# WS2812_MATRIX_6.net
KiCad netlist of a schematic drawn in Altium Designer
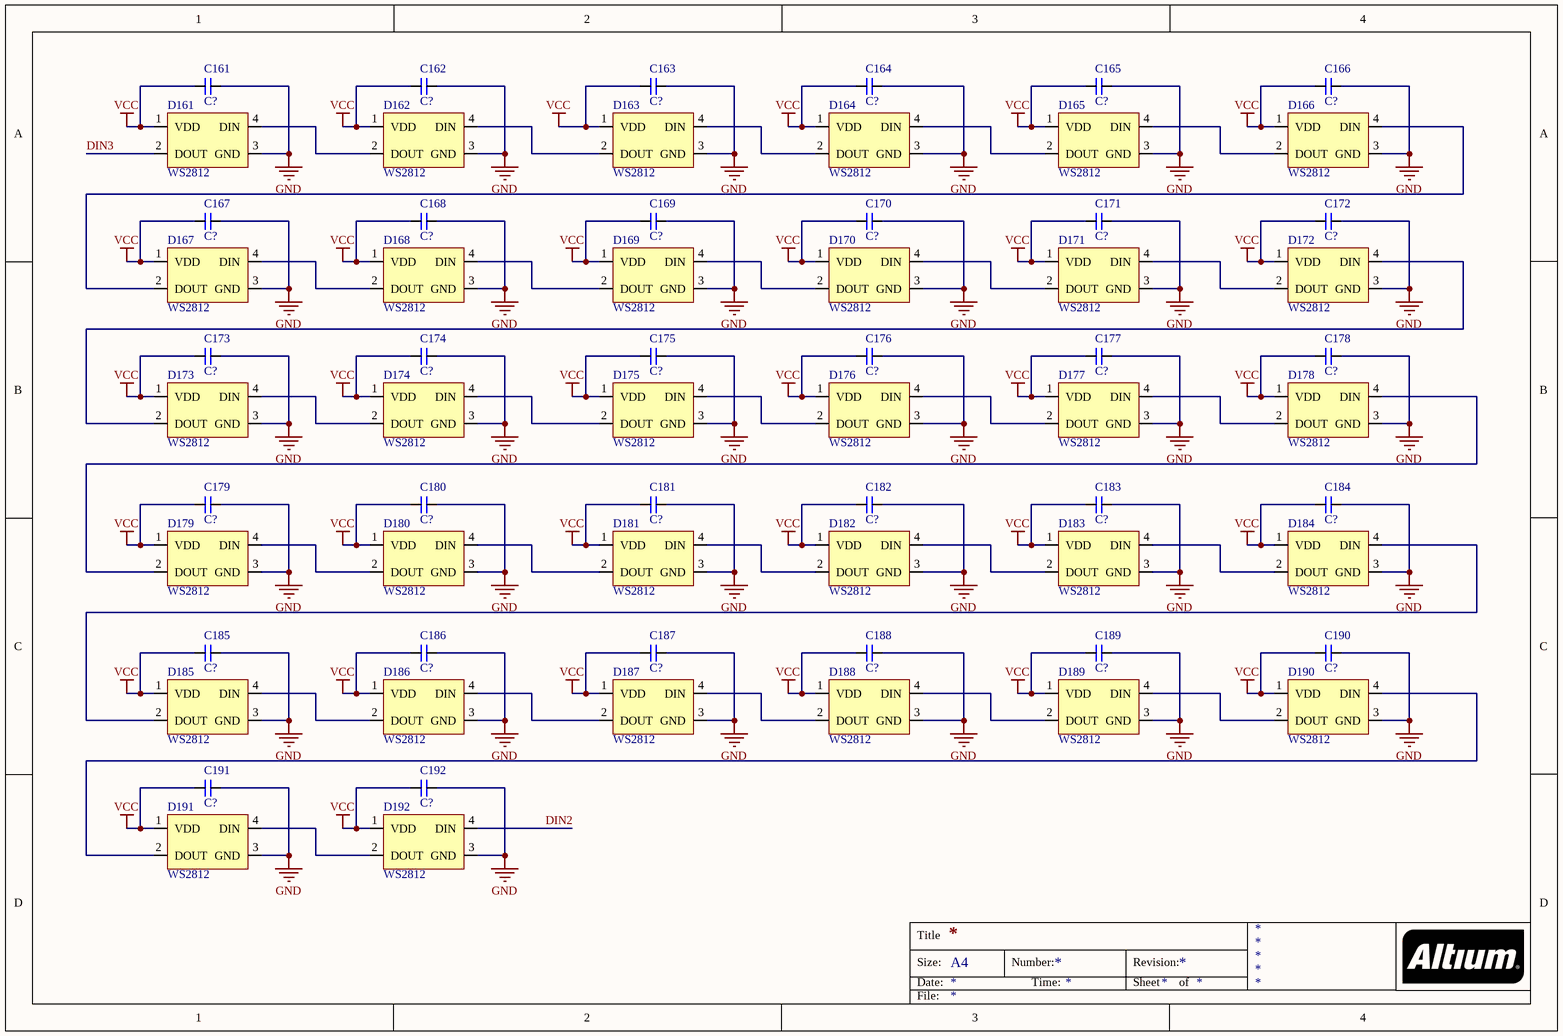
[diagram p0: WS2812_MATRIX_6.SchDoc]

(export (version "E")
  (design (tool "Eeschema 10.0.6"))
  (components
    (comp (ref "C161")
      (value "C?")
      (footprint "C0603")
      (description "Cap")
      (libsource (lib "SCH_Bacsic") (part "CAP"))
    )
    (comp (ref "C162")
      (value "C?")
      (footprint "C0603")
      (description "Cap")
      (libsource (lib "SCH_Bacsic") (part "CAP"))
    )
    (comp (ref "C163")
      (value "C?")
      (footprint "C0603")
      (description "Cap")
      (libsource (lib "SCH_Bacsic") (part "CAP"))
    )
    (comp (ref "C164")
      (value "C?")
      (footprint "C0603")
      (description "Cap")
      (libsource (lib "SCH_Bacsic") (part "CAP"))
    )
    (comp (ref "C165")
      (value "C?")
      (footprint "C0603")
      (description "Cap")
      (libsource (lib "SCH_Bacsic") (part "CAP"))
    )
    (comp (ref "C166")
      (value "C?")
      (footprint "C0603")
      (description "Cap")
      (libsource (lib "SCH_Bacsic") (part "CAP"))
    )
    (comp (ref "C167")
      (value "C?")
      (footprint "C0603")
      (description "Cap")
      (libsource (lib "SCH_Bacsic") (part "CAP"))
    )
    (comp (ref "C168")
      (value "C?")
      (footprint "C0603")
      (description "Cap")
      (libsource (lib "SCH_Bacsic") (part "CAP"))
    )
    (comp (ref "C169")
      (value "C?")
      (footprint "C0603")
      (description "Cap")
      (libsource (lib "SCH_Bacsic") (part "CAP"))
    )
    (comp (ref "C170")
      (value "C?")
      (footprint "C0603")
      (description "Cap")
      (libsource (lib "SCH_Bacsic") (part "CAP"))
    )
    (comp (ref "C171")
      (value "C?")
      (footprint "C0603")
      (description "Cap")
      (libsource (lib "SCH_Bacsic") (part "CAP"))
    )
    (comp (ref "C172")
      (value "C?")
      (footprint "C0603")
      (description "Cap")
      (libsource (lib "SCH_Bacsic") (part "CAP"))
    )
    (comp (ref "C173")
      (value "C?")
      (footprint "C0603")
      (description "Cap")
      (libsource (lib "SCH_Bacsic") (part "CAP"))
    )
    (comp (ref "C174")
      (value "C?")
      (footprint "C0603")
      (description "Cap")
      (libsource (lib "SCH_Bacsic") (part "CAP"))
    )
    (comp (ref "C175")
      (value "C?")
      (footprint "C0603")
      (description "Cap")
      (libsource (lib "SCH_Bacsic") (part "CAP"))
    )
    (comp (ref "C176")
      (value "C?")
      (footprint "C0603")
      (description "Cap")
      (libsource (lib "SCH_Bacsic") (part "CAP"))
    )
    (comp (ref "C177")
      (value "C?")
      (footprint "C0603")
      (description "Cap")
      (libsource (lib "SCH_Bacsic") (part "CAP"))
    )
    (comp (ref "C178")
      (value "C?")
      (footprint "C0603")
      (description "Cap")
      (libsource (lib "SCH_Bacsic") (part "CAP"))
    )
    (comp (ref "C179")
      (value "C?")
      (footprint "C0603")
      (description "Cap")
      (libsource (lib "SCH_Bacsic") (part "CAP"))
    )
    (comp (ref "C180")
      (value "C?")
      (footprint "C0603")
      (description "Cap")
      (libsource (lib "SCH_Bacsic") (part "CAP"))
    )
    (comp (ref "C181")
      (value "C?")
      (footprint "C0603")
      (description "Cap")
      (libsource (lib "SCH_Bacsic") (part "CAP"))
    )
    (comp (ref "C182")
      (value "C?")
      (footprint "C0603")
      (description "Cap")
      (libsource (lib "SCH_Bacsic") (part "CAP"))
    )
    (comp (ref "C183")
      (value "C?")
      (footprint "C0603")
      (description "Cap")
      (libsource (lib "SCH_Bacsic") (part "CAP"))
    )
    (comp (ref "C184")
      (value "C?")
      (footprint "C0603")
      (description "Cap")
      (libsource (lib "SCH_Bacsic") (part "CAP"))
    )
    (comp (ref "C185")
      (value "C?")
      (footprint "C0603")
      (description "Cap")
      (libsource (lib "SCH_Bacsic") (part "CAP"))
    )
    (comp (ref "C186")
      (value "C?")
      (footprint "C0603")
      (description "Cap")
      (libsource (lib "SCH_Bacsic") (part "CAP"))
    )
    (comp (ref "C187")
      (value "C?")
      (footprint "C0603")
      (description "Cap")
      (libsource (lib "SCH_Bacsic") (part "CAP"))
    )
    (comp (ref "C188")
      (value "C?")
      (footprint "C0603")
      (description "Cap")
      (libsource (lib "SCH_Bacsic") (part "CAP"))
    )
    (comp (ref "C189")
      (value "C?")
      (footprint "C0603")
      (description "Cap")
      (libsource (lib "SCH_Bacsic") (part "CAP"))
    )
    (comp (ref "C190")
      (value "C?")
      (footprint "C0603")
      (description "Cap")
      (libsource (lib "SCH_Bacsic") (part "CAP"))
    )
    (comp (ref "C191")
      (value "C?")
      (footprint "C0603")
      (description "Cap")
      (libsource (lib "SCH_Bacsic") (part "CAP"))
    )
    (comp (ref "C192")
      (value "C?")
      (footprint "C0603")
      (description "Cap")
      (libsource (lib "SCH_Bacsic") (part "CAP"))
    )
    (comp (ref "D161")
      (value "WS2812")
      (footprint "WS2812_3528")
      (libsource (lib "SCH_Bacsic") (part "WS2812"))
    )
    (comp (ref "D162")
      (value "WS2812")
      (footprint "WS2812_3528")
      (libsource (lib "SCH_Bacsic") (part "WS2812"))
    )
    (comp (ref "D163")
      (value "WS2812")
      (footprint "WS2812_3528")
      (libsource (lib "SCH_Bacsic") (part "WS2812"))
    )
    (comp (ref "D164")
      (value "WS2812")
      (footprint "WS2812_3528")
      (libsource (lib "SCH_Bacsic") (part "WS2812"))
    )
    (comp (ref "D165")
      (value "WS2812")
      (footprint "WS2812_3528")
      (libsource (lib "SCH_Bacsic") (part "WS2812"))
    )
    (comp (ref "D166")
      (value "WS2812")
      (footprint "WS2812_3528")
      (libsource (lib "SCH_Bacsic") (part "WS2812"))
    )
    (comp (ref "D167")
      (value "WS2812")
      (footprint "WS2812_3528")
      (libsource (lib "SCH_Bacsic") (part "WS2812"))
    )
    (comp (ref "D168")
      (value "WS2812")
      (footprint "WS2812_3528")
      (libsource (lib "SCH_Bacsic") (part "WS2812"))
    )
    (comp (ref "D169")
      (value "WS2812")
      (footprint "WS2812_3528")
      (libsource (lib "SCH_Bacsic") (part "WS2812"))
    )
    (comp (ref "D170")
      (value "WS2812")
      (footprint "WS2812_3528")
      (libsource (lib "SCH_Bacsic") (part "WS2812"))
    )
    (comp (ref "D171")
      (value "WS2812")
      (footprint "WS2812_3528")
      (libsource (lib "SCH_Bacsic") (part "WS2812"))
    )
    (comp (ref "D172")
      (value "WS2812")
      (footprint "WS2812_3528")
      (libsource (lib "SCH_Bacsic") (part "WS2812"))
    )
    (comp (ref "D173")
      (value "WS2812")
      (footprint "WS2812_3528")
      (libsource (lib "SCH_Bacsic") (part "WS2812"))
    )
    (comp (ref "D174")
      (value "WS2812")
      (footprint "WS2812_3528")
      (libsource (lib "SCH_Bacsic") (part "WS2812"))
    )
    (comp (ref "D175")
      (value "WS2812")
      (footprint "WS2812_3528")
      (libsource (lib "SCH_Bacsic") (part "WS2812"))
    )
    (comp (ref "D176")
      (value "WS2812")
      (footprint "WS2812_3528")
      (libsource (lib "SCH_Bacsic") (part "WS2812"))
    )
    (comp (ref "D177")
      (value "WS2812")
      (footprint "WS2812_3528")
      (libsource (lib "SCH_Bacsic") (part "WS2812"))
    )
    (comp (ref "D178")
      (value "WS2812")
      (footprint "WS2812_3528")
      (libsource (lib "SCH_Bacsic") (part "WS2812"))
    )
    (comp (ref "D179")
      (value "WS2812")
      (footprint "WS2812_3528")
      (libsource (lib "SCH_Bacsic") (part "WS2812"))
    )
    (comp (ref "D180")
      (value "WS2812")
      (footprint "WS2812_3528")
      (libsource (lib "SCH_Bacsic") (part "WS2812"))
    )
    (comp (ref "D181")
      (value "WS2812")
      (footprint "WS2812_3528")
      (libsource (lib "SCH_Bacsic") (part "WS2812"))
    )
    (comp (ref "D182")
      (value "WS2812")
      (footprint "WS2812_3528")
      (libsource (lib "SCH_Bacsic") (part "WS2812"))
    )
    (comp (ref "D183")
      (value "WS2812")
      (footprint "WS2812_3528")
      (libsource (lib "SCH_Bacsic") (part "WS2812"))
    )
    (comp (ref "D184")
      (value "WS2812")
      (footprint "WS2812_3528")
      (libsource (lib "SCH_Bacsic") (part "WS2812"))
    )
    (comp (ref "D185")
      (value "WS2812")
      (footprint "WS2812_3528")
      (libsource (lib "SCH_Bacsic") (part "WS2812"))
    )
    (comp (ref "D186")
      (value "WS2812")
      (footprint "WS2812_3528")
      (libsource (lib "SCH_Bacsic") (part "WS2812"))
    )
    (comp (ref "D187")
      (value "WS2812")
      (footprint "WS2812_3528")
      (libsource (lib "SCH_Bacsic") (part "WS2812"))
    )
    (comp (ref "D188")
      (value "WS2812")
      (footprint "WS2812_3528")
      (libsource (lib "SCH_Bacsic") (part "WS2812"))
    )
    (comp (ref "D189")
      (value "WS2812")
      (footprint "WS2812_3528")
      (libsource (lib "SCH_Bacsic") (part "WS2812"))
    )
    (comp (ref "D190")
      (value "WS2812")
      (footprint "WS2812_3528")
      (libsource (lib "SCH_Bacsic") (part "WS2812"))
    )
    (comp (ref "D191")
      (value "WS2812")
      (footprint "WS2812_3528")
      (libsource (lib "SCH_Bacsic") (part "WS2812"))
    )
    (comp (ref "D192")
      (value "WS2812")
      (footprint "WS2812_3528")
      (libsource (lib "SCH_Bacsic") (part "WS2812"))
    )
  )
  (nets
    (net (code "1") (name "/DIN2") (class "Default")
      (node (ref "D192") (pin "4") (pinfunction "DIN_4") (pintype "passive"))
    )
    (net (code "2") (name "/DIN3") (class "Default")
      (node (ref "D161") (pin "2") (pinfunction "DOUT_2") (pintype "passive"))
    )
    (net (code "3") (name "GND") (class "Default")
      (node (ref "C161") (pin "2") (pintype "passive"))
      (node (ref "C162") (pin "2") (pintype "passive"))
      (node (ref "C163") (pin "2") (pintype "passive"))
      (node (ref "C164") (pin "2") (pintype "passive"))
      (node (ref "C165") (pin "2") (pintype "passive"))
      (node (ref "C166") (pin "2") (pintype "passive"))
      (node (ref "C167") (pin "2") (pintype "passive"))
      (node (ref "C168") (pin "2") (pintype "passive"))
      (node (ref "C169") (pin "2") (pintype "passive"))
      (node (ref "C170") (pin "2") (pintype "passive"))
      (node (ref "C171") (pin "2") (pintype "passive"))
      (node (ref "C172") (pin "2") (pintype "passive"))
      (node (ref "C173") (pin "2") (pintype "passive"))
      (node (ref "C174") (pin "2") (pintype "passive"))
      (node (ref "C175") (pin "2") (pintype "passive"))
      (node (ref "C176") (pin "2") (pintype "passive"))
      (node (ref "C177") (pin "2") (pintype "passive"))
      (node (ref "C178") (pin "2") (pintype "passive"))
      (node (ref "C179") (pin "2") (pintype "passive"))
      (node (ref "C180") (pin "2") (pintype "passive"))
      (node (ref "C181") (pin "2") (pintype "passive"))
      (node (ref "C182") (pin "2") (pintype "passive"))
      (node (ref "C183") (pin "2") (pintype "passive"))
      (node (ref "C184") (pin "2") (pintype "passive"))
      (node (ref "C185") (pin "2") (pintype "passive"))
      (node (ref "C186") (pin "2") (pintype "passive"))
      (node (ref "C187") (pin "2") (pintype "passive"))
      (node (ref "C188") (pin "2") (pintype "passive"))
      (node (ref "C189") (pin "2") (pintype "passive"))
      (node (ref "C190") (pin "2") (pintype "passive"))
      (node (ref "C191") (pin "2") (pintype "passive"))
      (node (ref "C192") (pin "2") (pintype "passive"))
      (node (ref "D161") (pin "3") (pinfunction "GND_3") (pintype "passive"))
      (node (ref "D162") (pin "3") (pinfunction "GND_3") (pintype "passive"))
      (node (ref "D163") (pin "3") (pinfunction "GND_3") (pintype "passive"))
      (node (ref "D164") (pin "3") (pinfunction "GND_3") (pintype "passive"))
      (node (ref "D165") (pin "3") (pinfunction "GND_3") (pintype "passive"))
      (node (ref "D166") (pin "3") (pinfunction "GND_3") (pintype "passive"))
      (node (ref "D167") (pin "3") (pinfunction "GND_3") (pintype "passive"))
      (node (ref "D168") (pin "3") (pinfunction "GND_3") (pintype "passive"))
      (node (ref "D169") (pin "3") (pinfunction "GND_3") (pintype "passive"))
      (node (ref "D170") (pin "3") (pinfunction "GND_3") (pintype "passive"))
      (node (ref "D171") (pin "3") (pinfunction "GND_3") (pintype "passive"))
      (node (ref "D172") (pin "3") (pinfunction "GND_3") (pintype "passive"))
      (node (ref "D173") (pin "3") (pinfunction "GND_3") (pintype "passive"))
      (node (ref "D174") (pin "3") (pinfunction "GND_3") (pintype "passive"))
      (node (ref "D175") (pin "3") (pinfunction "GND_3") (pintype "passive"))
      (node (ref "D176") (pin "3") (pinfunction "GND_3") (pintype "passive"))
      (node (ref "D177") (pin "3") (pinfunction "GND_3") (pintype "passive"))
      (node (ref "D178") (pin "3") (pinfunction "GND_3") (pintype "passive"))
      (node (ref "D179") (pin "3") (pinfunction "GND_3") (pintype "passive"))
      (node (ref "D180") (pin "3") (pinfunction "GND_3") (pintype "passive"))
      (node (ref "D181") (pin "3") (pinfunction "GND_3") (pintype "passive"))
      (node (ref "D182") (pin "3") (pinfunction "GND_3") (pintype "passive"))
      (node (ref "D183") (pin "3") (pinfunction "GND_3") (pintype "passive"))
      (node (ref "D184") (pin "3") (pinfunction "GND_3") (pintype "passive"))
      (node (ref "D185") (pin "3") (pinfunction "GND_3") (pintype "passive"))
      (node (ref "D186") (pin "3") (pinfunction "GND_3") (pintype "passive"))
      (node (ref "D187") (pin "3") (pinfunction "GND_3") (pintype "passive"))
      (node (ref "D188") (pin "3") (pinfunction "GND_3") (pintype "passive"))
      (node (ref "D189") (pin "3") (pinfunction "GND_3") (pintype "passive"))
      (node (ref "D190") (pin "3") (pinfunction "GND_3") (pintype "passive"))
      (node (ref "D191") (pin "3") (pinfunction "GND_3") (pintype "passive"))
      (node (ref "D192") (pin "3") (pinfunction "GND_3") (pintype "passive"))
    )
    (net (code "4") (name "Net-(D161-DIN)") (class "Default")
      (node (ref "D161") (pin "4") (pinfunction "DIN_4") (pintype "passive"))
      (node (ref "D162") (pin "2") (pinfunction "DOUT_2") (pintype "passive"))
    )
    (net (code "5") (name "Net-(D162-DIN)") (class "Default")
      (node (ref "D162") (pin "4") (pinfunction "DIN_4") (pintype "passive"))
      (node (ref "D163") (pin "2") (pinfunction "DOUT_2") (pintype "passive"))
    )
    (net (code "6") (name "Net-(D163-DIN)") (class "Default")
      (node (ref "D163") (pin "4") (pinfunction "DIN_4") (pintype "passive"))
      (node (ref "D164") (pin "2") (pinfunction "DOUT_2") (pintype "passive"))
    )
    (net (code "7") (name "Net-(D164-DIN)") (class "Default")
      (node (ref "D164") (pin "4") (pinfunction "DIN_4") (pintype "passive"))
      (node (ref "D165") (pin "2") (pinfunction "DOUT_2") (pintype "passive"))
    )
    (net (code "8") (name "Net-(D165-DIN)") (class "Default")
      (node (ref "D165") (pin "4") (pinfunction "DIN_4") (pintype "passive"))
      (node (ref "D166") (pin "2") (pinfunction "DOUT_2") (pintype "passive"))
    )
    (net (code "9") (name "Net-(D166-DIN)") (class "Default")
      (node (ref "D166") (pin "4") (pinfunction "DIN_4") (pintype "passive"))
      (node (ref "D167") (pin "2") (pinfunction "DOUT_2") (pintype "passive"))
    )
    (net (code "10") (name "Net-(D167-DIN)") (class "Default")
      (node (ref "D167") (pin "4") (pinfunction "DIN_4") (pintype "passive"))
      (node (ref "D168") (pin "2") (pinfunction "DOUT_2") (pintype "passive"))
    )
    (net (code "11") (name "Net-(D168-DIN)") (class "Default")
      (node (ref "D168") (pin "4") (pinfunction "DIN_4") (pintype "passive"))
      (node (ref "D169") (pin "2") (pinfunction "DOUT_2") (pintype "passive"))
    )
    (net (code "12") (name "Net-(D169-DIN)") (class "Default")
      (node (ref "D169") (pin "4") (pinfunction "DIN_4") (pintype "passive"))
      (node (ref "D170") (pin "2") (pinfunction "DOUT_2") (pintype "passive"))
    )
    (net (code "13") (name "Net-(D170-DIN)") (class "Default")
      (node (ref "D170") (pin "4") (pinfunction "DIN_4") (pintype "passive"))
      (node (ref "D171") (pin "2") (pinfunction "DOUT_2") (pintype "passive"))
    )
    (net (code "14") (name "Net-(D171-DIN)") (class "Default")
      (node (ref "D171") (pin "4") (pinfunction "DIN_4") (pintype "passive"))
      (node (ref "D172") (pin "2") (pinfunction "DOUT_2") (pintype "passive"))
    )
    (net (code "15") (name "Net-(D172-DIN)") (class "Default")
      (node (ref "D172") (pin "4") (pinfunction "DIN_4") (pintype "passive"))
      (node (ref "D173") (pin "2") (pinfunction "DOUT_2") (pintype "passive"))
    )
    (net (code "16") (name "Net-(D173-DIN)") (class "Default")
      (node (ref "D173") (pin "4") (pinfunction "DIN_4") (pintype "passive"))
      (node (ref "D174") (pin "2") (pinfunction "DOUT_2") (pintype "passive"))
    )
    (net (code "17") (name "Net-(D174-DIN)") (class "Default")
      (node (ref "D174") (pin "4") (pinfunction "DIN_4") (pintype "passive"))
      (node (ref "D175") (pin "2") (pinfunction "DOUT_2") (pintype "passive"))
    )
    (net (code "18") (name "Net-(D175-DIN)") (class "Default")
      (node (ref "D175") (pin "4") (pinfunction "DIN_4") (pintype "passive"))
      (node (ref "D176") (pin "2") (pinfunction "DOUT_2") (pintype "passive"))
    )
    (net (code "19") (name "Net-(D176-DIN)") (class "Default")
      (node (ref "D176") (pin "4") (pinfunction "DIN_4") (pintype "passive"))
      (node (ref "D177") (pin "2") (pinfunction "DOUT_2") (pintype "passive"))
    )
    (net (code "20") (name "Net-(D177-DIN)") (class "Default")
      (node (ref "D177") (pin "4") (pinfunction "DIN_4") (pintype "passive"))
      (node (ref "D178") (pin "2") (pinfunction "DOUT_2") (pintype "passive"))
    )
    (net (code "21") (name "Net-(D178-DIN)") (class "Default")
      (node (ref "D178") (pin "4") (pinfunction "DIN_4") (pintype "passive"))
      (node (ref "D179") (pin "2") (pinfunction "DOUT_2") (pintype "passive"))
    )
    (net (code "22") (name "Net-(D179-DIN)") (class "Default")
      (node (ref "D179") (pin "4") (pinfunction "DIN_4") (pintype "passive"))
      (node (ref "D180") (pin "2") (pinfunction "DOUT_2") (pintype "passive"))
    )
    (net (code "23") (name "Net-(D180-DIN)") (class "Default")
      (node (ref "D180") (pin "4") (pinfunction "DIN_4") (pintype "passive"))
      (node (ref "D181") (pin "2") (pinfunction "DOUT_2") (pintype "passive"))
    )
    (net (code "24") (name "Net-(D181-DIN)") (class "Default")
      (node (ref "D181") (pin "4") (pinfunction "DIN_4") (pintype "passive"))
      (node (ref "D182") (pin "2") (pinfunction "DOUT_2") (pintype "passive"))
    )
    (net (code "25") (name "Net-(D182-DIN)") (class "Default")
      (node (ref "D182") (pin "4") (pinfunction "DIN_4") (pintype "passive"))
      (node (ref "D183") (pin "2") (pinfunction "DOUT_2") (pintype "passive"))
    )
    (net (code "26") (name "Net-(D183-DIN)") (class "Default")
      (node (ref "D183") (pin "4") (pinfunction "DIN_4") (pintype "passive"))
      (node (ref "D184") (pin "2") (pinfunction "DOUT_2") (pintype "passive"))
    )
    (net (code "27") (name "Net-(D184-DIN)") (class "Default")
      (node (ref "D184") (pin "4") (pinfunction "DIN_4") (pintype "passive"))
      (node (ref "D185") (pin "2") (pinfunction "DOUT_2") (pintype "passive"))
    )
    (net (code "28") (name "Net-(D185-DIN)") (class "Default")
      (node (ref "D185") (pin "4") (pinfunction "DIN_4") (pintype "passive"))
      (node (ref "D186") (pin "2") (pinfunction "DOUT_2") (pintype "passive"))
    )
    (net (code "29") (name "Net-(D186-DIN)") (class "Default")
      (node (ref "D186") (pin "4") (pinfunction "DIN_4") (pintype "passive"))
      (node (ref "D187") (pin "2") (pinfunction "DOUT_2") (pintype "passive"))
    )
    (net (code "30") (name "Net-(D187-DIN)") (class "Default")
      (node (ref "D187") (pin "4") (pinfunction "DIN_4") (pintype "passive"))
      (node (ref "D188") (pin "2") (pinfunction "DOUT_2") (pintype "passive"))
    )
    (net (code "31") (name "Net-(D188-DIN)") (class "Default")
      (node (ref "D188") (pin "4") (pinfunction "DIN_4") (pintype "passive"))
      (node (ref "D189") (pin "2") (pinfunction "DOUT_2") (pintype "passive"))
    )
    (net (code "32") (name "Net-(D189-DIN)") (class "Default")
      (node (ref "D189") (pin "4") (pinfunction "DIN_4") (pintype "passive"))
      (node (ref "D190") (pin "2") (pinfunction "DOUT_2") (pintype "passive"))
    )
    (net (code "33") (name "Net-(D190-DIN)") (class "Default")
      (node (ref "D190") (pin "4") (pinfunction "DIN_4") (pintype "passive"))
      (node (ref "D191") (pin "2") (pinfunction "DOUT_2") (pintype "passive"))
    )
    (net (code "34") (name "Net-(D191-DIN)") (class "Default")
      (node (ref "D191") (pin "4") (pinfunction "DIN_4") (pintype "passive"))
      (node (ref "D192") (pin "2") (pinfunction "DOUT_2") (pintype "passive"))
    )
    (net (code "35") (name "VCC") (class "Default")
      (node (ref "C161") (pin "1") (pintype "passive"))
      (node (ref "C162") (pin "1") (pintype "passive"))
      (node (ref "C163") (pin "1") (pintype "passive"))
      (node (ref "C164") (pin "1") (pintype "passive"))
      (node (ref "C165") (pin "1") (pintype "passive"))
      (node (ref "C166") (pin "1") (pintype "passive"))
      (node (ref "C167") (pin "1") (pintype "passive"))
      (node (ref "C168") (pin "1") (pintype "passive"))
      (node (ref "C169") (pin "1") (pintype "passive"))
      (node (ref "C170") (pin "1") (pintype "passive"))
      (node (ref "C171") (pin "1") (pintype "passive"))
      (node (ref "C172") (pin "1") (pintype "passive"))
      (node (ref "C173") (pin "1") (pintype "passive"))
      (node (ref "C174") (pin "1") (pintype "passive"))
      (node (ref "C175") (pin "1") (pintype "passive"))
      (node (ref "C176") (pin "1") (pintype "passive"))
      (node (ref "C177") (pin "1") (pintype "passive"))
      (node (ref "C178") (pin "1") (pintype "passive"))
      (node (ref "C179") (pin "1") (pintype "passive"))
      (node (ref "C180") (pin "1") (pintype "passive"))
      (node (ref "C181") (pin "1") (pintype "passive"))
      (node (ref "C182") (pin "1") (pintype "passive"))
      (node (ref "C183") (pin "1") (pintype "passive"))
      (node (ref "C184") (pin "1") (pintype "passive"))
      (node (ref "C185") (pin "1") (pintype "passive"))
      (node (ref "C186") (pin "1") (pintype "passive"))
      (node (ref "C187") (pin "1") (pintype "passive"))
      (node (ref "C188") (pin "1") (pintype "passive"))
      (node (ref "C189") (pin "1") (pintype "passive"))
      (node (ref "C190") (pin "1") (pintype "passive"))
      (node (ref "C191") (pin "1") (pintype "passive"))
      (node (ref "C192") (pin "1") (pintype "passive"))
      (node (ref "D161") (pin "1") (pinfunction "VDD_1") (pintype "passive"))
      (node (ref "D162") (pin "1") (pinfunction "VDD_1") (pintype "passive"))
      (node (ref "D163") (pin "1") (pinfunction "VDD_1") (pintype "passive"))
      (node (ref "D164") (pin "1") (pinfunction "VDD_1") (pintype "passive"))
      (node (ref "D165") (pin "1") (pinfunction "VDD_1") (pintype "passive"))
      (node (ref "D166") (pin "1") (pinfunction "VDD_1") (pintype "passive"))
      (node (ref "D167") (pin "1") (pinfunction "VDD_1") (pintype "passive"))
      (node (ref "D168") (pin "1") (pinfunction "VDD_1") (pintype "passive"))
      (node (ref "D169") (pin "1") (pinfunction "VDD_1") (pintype "passive"))
      (node (ref "D170") (pin "1") (pinfunction "VDD_1") (pintype "passive"))
      (node (ref "D171") (pin "1") (pinfunction "VDD_1") (pintype "passive"))
      (node (ref "D172") (pin "1") (pinfunction "VDD_1") (pintype "passive"))
      (node (ref "D173") (pin "1") (pinfunction "VDD_1") (pintype "passive"))
      (node (ref "D174") (pin "1") (pinfunction "VDD_1") (pintype "passive"))
      (node (ref "D175") (pin "1") (pinfunction "VDD_1") (pintype "passive"))
      (node (ref "D176") (pin "1") (pinfunction "VDD_1") (pintype "passive"))
      (node (ref "D177") (pin "1") (pinfunction "VDD_1") (pintype "passive"))
      (node (ref "D178") (pin "1") (pinfunction "VDD_1") (pintype "passive"))
      (node (ref "D179") (pin "1") (pinfunction "VDD_1") (pintype "passive"))
      (node (ref "D180") (pin "1") (pinfunction "VDD_1") (pintype "passive"))
      (node (ref "D181") (pin "1") (pinfunction "VDD_1") (pintype "passive"))
      (node (ref "D182") (pin "1") (pinfunction "VDD_1") (pintype "passive"))
      (node (ref "D183") (pin "1") (pinfunction "VDD_1") (pintype "passive"))
      (node (ref "D184") (pin "1") (pinfunction "VDD_1") (pintype "passive"))
      (node (ref "D185") (pin "1") (pinfunction "VDD_1") (pintype "passive"))
      (node (ref "D186") (pin "1") (pinfunction "VDD_1") (pintype "passive"))
      (node (ref "D187") (pin "1") (pinfunction "VDD_1") (pintype "passive"))
      (node (ref "D188") (pin "1") (pinfunction "VDD_1") (pintype "passive"))
      (node (ref "D189") (pin "1") (pinfunction "VDD_1") (pintype "passive"))
      (node (ref "D190") (pin "1") (pinfunction "VDD_1") (pintype "passive"))
      (node (ref "D191") (pin "1") (pinfunction "VDD_1") (pintype "passive"))
      (node (ref "D192") (pin "1") (pinfunction "VDD_1") (pintype "passive"))
    )
  )
)
